# TRI-LIMIT-INTERFACE.net
KiCad netlist of a schematic drawn in EAGLE
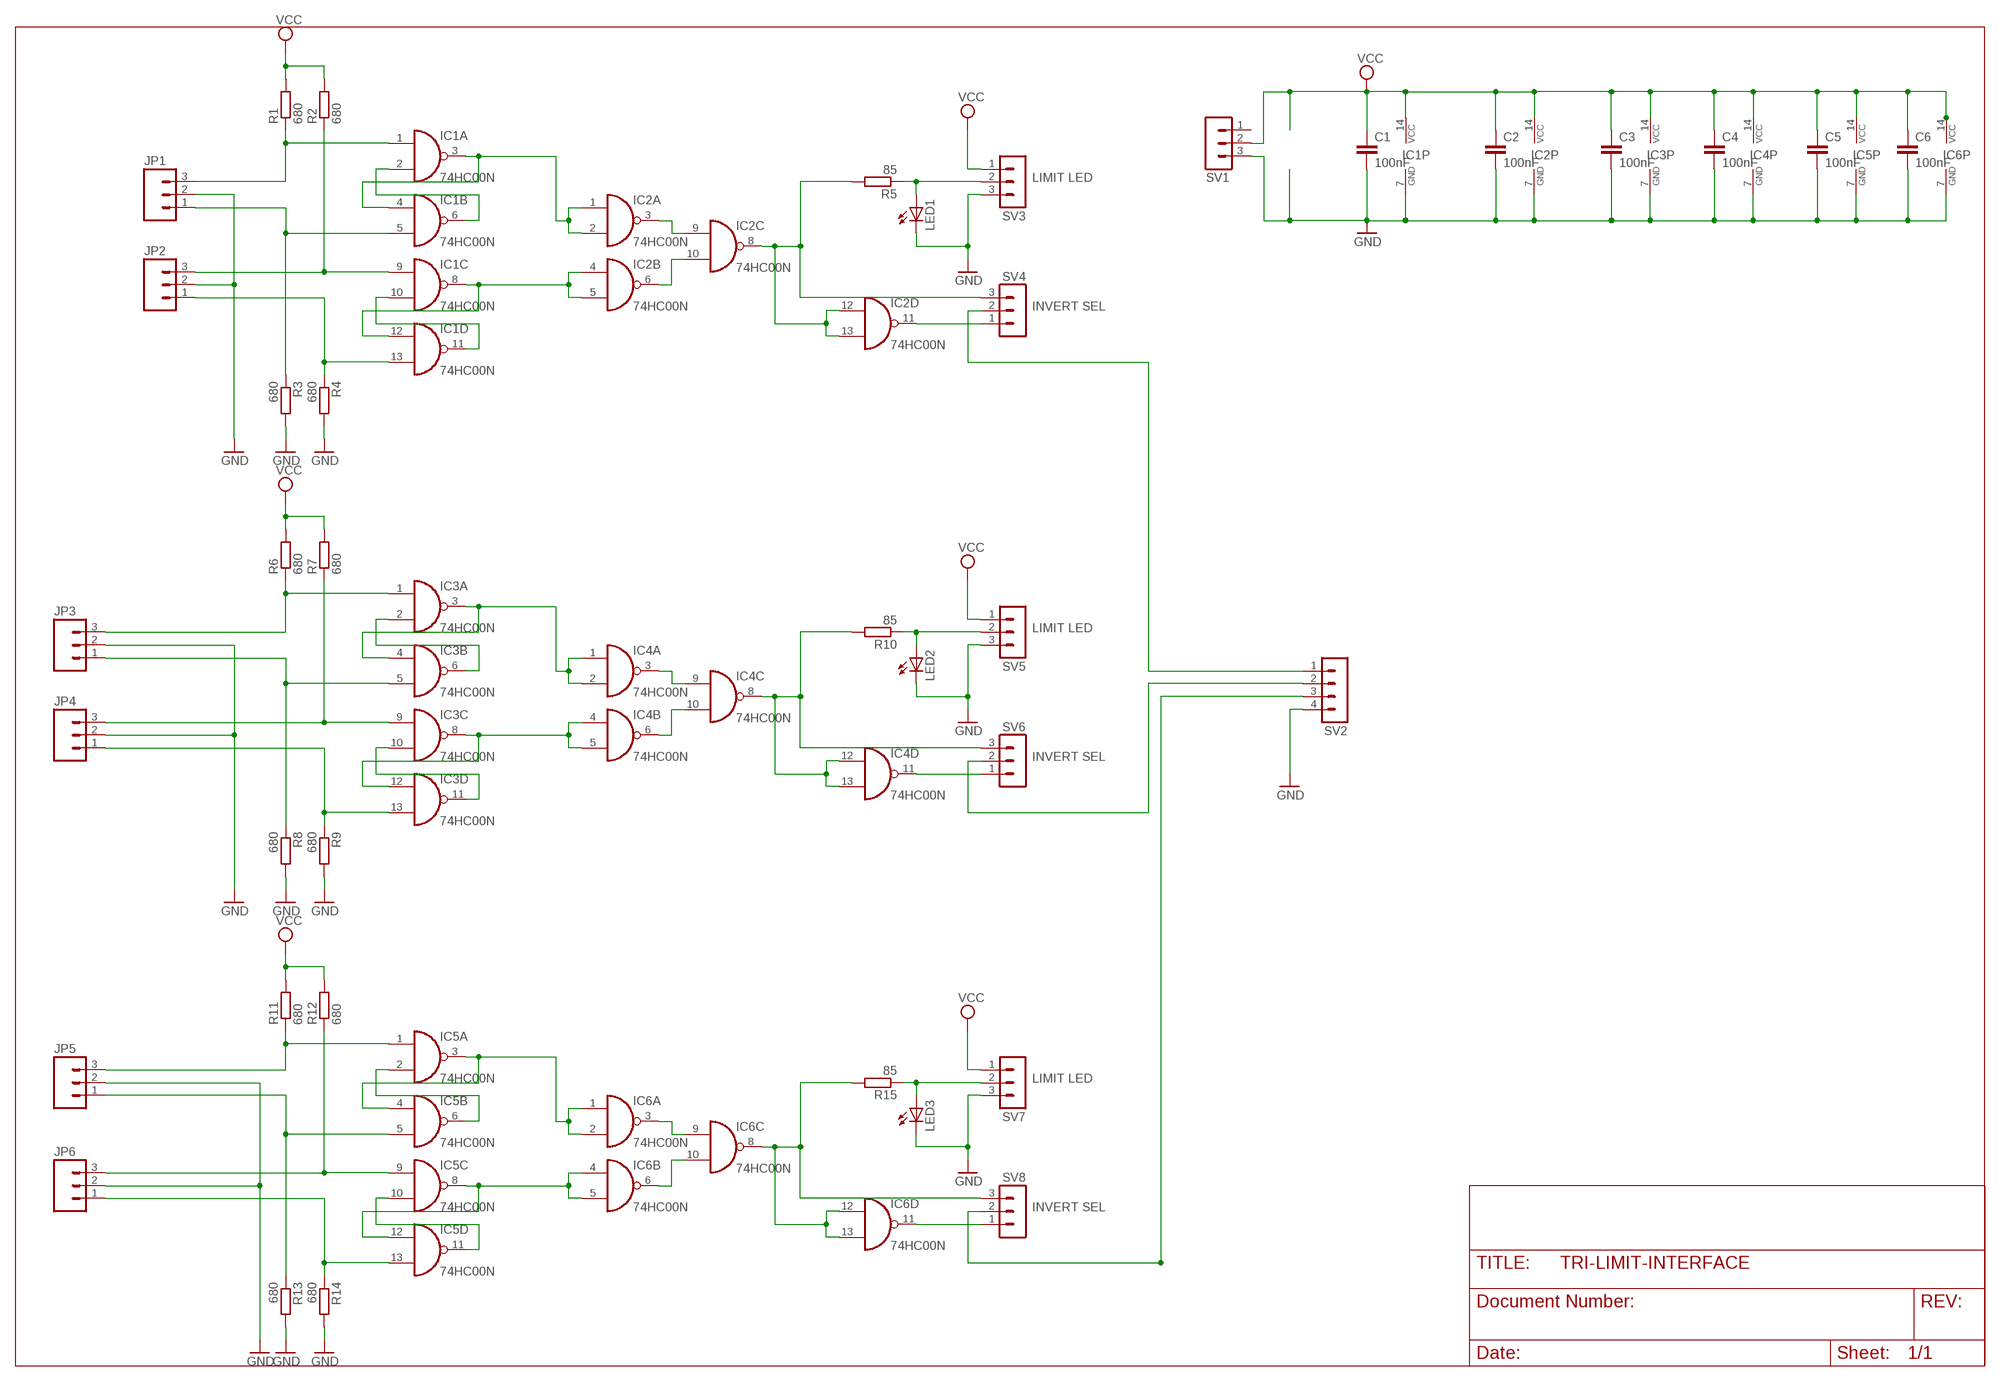
[diagram p0: schematic, sheet 1]

(export (version "E")
  (design (tool "Eeschema 10.0.6"))
  (components
    (comp (ref "C1")
      (value "100nF")
      (footprint "eagle-import:CAP-PTH-SMALL")
      (libsource (lib "eagle-import") (part "CAPPTH"))
    )
    (comp (ref "C2")
      (value "100nF")
      (footprint "eagle-import:CAP-PTH-SMALL")
      (libsource (lib "eagle-import") (part "CAPPTH"))
    )
    (comp (ref "C3")
      (value "100nF")
      (footprint "eagle-import:CAP-PTH-SMALL")
      (libsource (lib "eagle-import") (part "CAPPTH"))
    )
    (comp (ref "C4")
      (value "100nF")
      (footprint "eagle-import:CAP-PTH-SMALL")
      (libsource (lib "eagle-import") (part "CAPPTH"))
    )
    (comp (ref "C5")
      (value "100nF")
      (footprint "eagle-import:CAP-PTH-SMALL")
      (libsource (lib "eagle-import") (part "CAPPTH"))
    )
    (comp (ref "C6")
      (value "100nF")
      (footprint "eagle-import:CAP-PTH-SMALL")
      (libsource (lib "eagle-import") (part "CAPPTH"))
    )
    (comp (ref "IC1")
      (value "74HC00N")
      (footprint "eagle-import:DIL14")
      (libsource (lib "eagle-import") (part "7400NHC"))
    )
    (comp (ref "IC2")
      (value "74HC00N")
      (footprint "eagle-import:DIL14")
      (libsource (lib "eagle-import") (part "7400NHC"))
    )
    (comp (ref "IC3")
      (value "74HC00N")
      (footprint "eagle-import:DIL14")
      (libsource (lib "eagle-import") (part "7400NHC"))
    )
    (comp (ref "IC4")
      (value "74HC00N")
      (footprint "eagle-import:DIL14")
      (libsource (lib "eagle-import") (part "7400NHC"))
    )
    (comp (ref "IC5")
      (value "74HC00N")
      (footprint "eagle-import:DIL14")
      (libsource (lib "eagle-import") (part "7400NHC"))
    )
    (comp (ref "IC6")
      (value "74HC00N")
      (footprint "eagle-import:DIL14")
      (libsource (lib "eagle-import") (part "7400NHC"))
    )
    (comp (ref "JP1")
      (value "M03-SCREW-5MM")
      (footprint "eagle-import:SCREWTERMINAL-5MM-3")
      (libsource (lib "eagle-import") (part "M03-SCREW-5MM"))
    )
    (comp (ref "JP2")
      (value "M03-SCREW-5MM")
      (footprint "eagle-import:SCREWTERMINAL-5MM-3")
      (libsource (lib "eagle-import") (part "M03-SCREW-5MM"))
    )
    (comp (ref "JP3")
      (value "M03-SCREW-5MM")
      (footprint "eagle-import:SCREWTERMINAL-5MM-3")
      (libsource (lib "eagle-import") (part "M03-SCREW-5MM"))
    )
    (comp (ref "JP4")
      (value "M03-SCREW-5MM")
      (footprint "eagle-import:SCREWTERMINAL-5MM-3")
      (libsource (lib "eagle-import") (part "M03-SCREW-5MM"))
    )
    (comp (ref "JP5")
      (value "M03-SCREW-5MM")
      (footprint "eagle-import:SCREWTERMINAL-5MM-3")
      (libsource (lib "eagle-import") (part "M03-SCREW-5MM"))
    )
    (comp (ref "JP6")
      (value "M03-SCREW-5MM")
      (footprint "eagle-import:SCREWTERMINAL-5MM-3")
      (libsource (lib "eagle-import") (part "M03-SCREW-5MM"))
    )
    (comp (ref "LED1")
      (value "LED3MM")
      (footprint "eagle-import:LED3MM")
      (libsource (lib "eagle-import") (part "LED3MM"))
    )
    (comp (ref "LED2")
      (value "LED3MM")
      (footprint "eagle-import:LED3MM")
      (libsource (lib "eagle-import") (part "LED3MM"))
    )
    (comp (ref "LED3")
      (value "LED3MM")
      (footprint "eagle-import:LED3MM")
      (libsource (lib "eagle-import") (part "LED3MM"))
    )
    (comp (ref "R1")
      (value "680")
      (footprint "eagle-import:0207_7")
      (libsource (lib "eagle-import") (part "R-EU_0207/7"))
    )
    (comp (ref "R2")
      (value "680")
      (footprint "eagle-import:0207_7")
      (libsource (lib "eagle-import") (part "R-EU_0207/7"))
    )
    (comp (ref "R3")
      (value "680")
      (footprint "eagle-import:0207_7")
      (libsource (lib "eagle-import") (part "R-EU_0207/7"))
    )
    (comp (ref "R4")
      (value "680")
      (footprint "eagle-import:0207_7")
      (libsource (lib "eagle-import") (part "R-EU_0207/7"))
    )
    (comp (ref "R5")
      (value "85")
      (footprint "eagle-import:0207_10")
      (libsource (lib "eagle-import") (part "R-EU_0207/10"))
    )
    (comp (ref "R6")
      (value "680")
      (footprint "eagle-import:0207_7")
      (libsource (lib "eagle-import") (part "R-EU_0207/7"))
    )
    (comp (ref "R7")
      (value "680")
      (footprint "eagle-import:0207_7")
      (libsource (lib "eagle-import") (part "R-EU_0207/7"))
    )
    (comp (ref "R8")
      (value "680")
      (footprint "eagle-import:0207_7")
      (libsource (lib "eagle-import") (part "R-EU_0207/7"))
    )
    (comp (ref "R9")
      (value "680")
      (footprint "eagle-import:0207_7")
      (libsource (lib "eagle-import") (part "R-EU_0207/7"))
    )
    (comp (ref "R10")
      (value "85")
      (footprint "eagle-import:0207_10")
      (libsource (lib "eagle-import") (part "R-EU_0207/10"))
    )
    (comp (ref "R11")
      (value "680")
      (footprint "eagle-import:0207_7")
      (libsource (lib "eagle-import") (part "R-EU_0207/7"))
    )
    (comp (ref "R12")
      (value "680")
      (footprint "eagle-import:0207_7")
      (libsource (lib "eagle-import") (part "R-EU_0207/7"))
    )
    (comp (ref "R13")
      (value "680")
      (footprint "eagle-import:0207_7")
      (libsource (lib "eagle-import") (part "R-EU_0207/7"))
    )
    (comp (ref "R14")
      (value "680")
      (footprint "eagle-import:0207_7")
      (libsource (lib "eagle-import") (part "R-EU_0207/7"))
    )
    (comp (ref "R15")
      (value "85")
      (footprint "eagle-import:0207_10")
      (libsource (lib "eagle-import") (part "R-EU_0207/10"))
    )
    (comp (ref "SV1")
      (value "MA03-1")
      (footprint "eagle-import:MA03-1")
      (libsource (lib "eagle-import") (part "MA03-1"))
    )
    (comp (ref "SV2")
      (value "MA04-1")
      (footprint "eagle-import:MA04-1")
      (libsource (lib "eagle-import") (part "MA04-1"))
    )
    (comp (ref "SV3")
      (value "MA03-1")
      (footprint "eagle-import:MA03-1")
      (libsource (lib "eagle-import") (part "MA03-1"))
    )
    (comp (ref "SV4")
      (value "MA03-1")
      (footprint "eagle-import:MA03-1")
      (libsource (lib "eagle-import") (part "MA03-1"))
    )
    (comp (ref "SV5")
      (value "MA03-1")
      (footprint "eagle-import:MA03-1")
      (libsource (lib "eagle-import") (part "MA03-1"))
    )
    (comp (ref "SV6")
      (value "MA03-1")
      (footprint "eagle-import:MA03-1")
      (libsource (lib "eagle-import") (part "MA03-1"))
    )
    (comp (ref "SV7")
      (value "MA03-1")
      (footprint "eagle-import:MA03-1")
      (libsource (lib "eagle-import") (part "MA03-1"))
    )
    (comp (ref "SV8")
      (value "MA03-1")
      (footprint "eagle-import:MA03-1")
      (libsource (lib "eagle-import") (part "MA03-1"))
    )
  )
  (nets
    (net (code "1") (name "GND") (class "Default")
      (node (ref "C1") (pin "2") (pinfunction "2_2") (pintype "passive"))
      (node (ref "C2") (pin "2") (pinfunction "2_2") (pintype "passive"))
      (node (ref "C3") (pin "2") (pinfunction "2_2") (pintype "passive"))
      (node (ref "C4") (pin "2") (pinfunction "2_2") (pintype "passive"))
      (node (ref "C5") (pin "2") (pinfunction "2_2") (pintype "passive"))
      (node (ref "C6") (pin "2") (pinfunction "2_2") (pintype "passive"))
      (node (ref "IC1") (pin "7") (pinfunction "GND_7") (pintype "power_in"))
      (node (ref "IC2") (pin "7") (pinfunction "GND_7") (pintype "power_in"))
      (node (ref "IC3") (pin "7") (pinfunction "GND_7") (pintype "power_in"))
      (node (ref "IC4") (pin "7") (pinfunction "GND_7") (pintype "power_in"))
      (node (ref "IC5") (pin "7") (pinfunction "GND_7") (pintype "power_in"))
      (node (ref "IC6") (pin "7") (pinfunction "GND_7") (pintype "power_in"))
      (node (ref "JP1") (pin "2") (pinfunction "2_2") (pintype "passive"))
      (node (ref "JP2") (pin "2") (pinfunction "2_2") (pintype "passive"))
      (node (ref "JP3") (pin "2") (pinfunction "2_2") (pintype "passive"))
      (node (ref "JP4") (pin "2") (pinfunction "2_2") (pintype "passive"))
      (node (ref "JP5") (pin "2") (pinfunction "2_2") (pintype "passive"))
      (node (ref "JP6") (pin "2") (pinfunction "2_2") (pintype "passive"))
      (node (ref "LED1") (pin "K") (pinfunction "C_K") (pintype "passive"))
      (node (ref "LED2") (pin "K") (pinfunction "C_K") (pintype "passive"))
      (node (ref "LED3") (pin "K") (pinfunction "C_K") (pintype "passive"))
      (node (ref "R13") (pin "2") (pinfunction "2_2") (pintype "passive"))
      (node (ref "R14") (pin "2") (pinfunction "2_2") (pintype "passive"))
      (node (ref "R3") (pin "2") (pinfunction "2_2") (pintype "passive"))
      (node (ref "R4") (pin "2") (pinfunction "2_2") (pintype "passive"))
      (node (ref "R8") (pin "2") (pinfunction "2_2") (pintype "passive"))
      (node (ref "R9") (pin "2") (pinfunction "2_2") (pintype "passive"))
      (node (ref "SV1") (pin "3") (pinfunction "3_3") (pintype "passive"))
      (node (ref "SV2") (pin "4") (pinfunction "4_4") (pintype "passive"))
      (node (ref "SV3") (pin "3") (pinfunction "3_3") (pintype "passive"))
      (node (ref "SV5") (pin "3") (pinfunction "3_3") (pintype "passive"))
      (node (ref "SV7") (pin "3") (pinfunction "3_3") (pintype "passive"))
    )
    (net (code "2") (name "Net-(IC1A-I0)") (class "Default")
      (node (ref "IC1") (pin "1") (pinfunction "I0_1") (pintype "input"))
      (node (ref "JP1") (pin "3") (pinfunction "3_3") (pintype "passive"))
      (node (ref "R1") (pin "1") (pinfunction "1_1") (pintype "passive"))
    )
    (net (code "3") (name "Net-(IC1A-I1)") (class "Default")
      (node (ref "IC1") (pin "2") (pinfunction "I1_2") (pintype "input"))
      (node (ref "IC1") (pin "6") (pinfunction "O_6") (pintype "output"))
    )
    (net (code "4") (name "Net-(IC1A-O)") (class "Default")
      (node (ref "IC1") (pin "3") (pinfunction "O_3") (pintype "output"))
      (node (ref "IC1") (pin "4") (pinfunction "I0_4") (pintype "input"))
      (node (ref "IC2") (pin "1") (pinfunction "I0_1") (pintype "input"))
      (node (ref "IC2") (pin "2") (pinfunction "I1_2") (pintype "input"))
    )
    (net (code "5") (name "Net-(IC1B-I1)") (class "Default")
      (node (ref "IC1") (pin "5") (pinfunction "I1_5") (pintype "input"))
      (node (ref "JP1") (pin "1") (pinfunction "1_1") (pintype "passive"))
      (node (ref "R3") (pin "1") (pinfunction "1_1") (pintype "passive"))
    )
    (net (code "6") (name "Net-(IC1C-I0)") (class "Default")
      (node (ref "IC1") (pin "9") (pinfunction "I0_9") (pintype "input"))
      (node (ref "JP2") (pin "3") (pinfunction "3_3") (pintype "passive"))
      (node (ref "R2") (pin "1") (pinfunction "1_1") (pintype "passive"))
    )
    (net (code "7") (name "Net-(IC1C-I1)") (class "Default")
      (node (ref "IC1") (pin "10") (pinfunction "I1_10") (pintype "input"))
      (node (ref "IC1") (pin "11") (pinfunction "O_11") (pintype "output"))
    )
    (net (code "8") (name "Net-(IC1C-O)") (class "Default")
      (node (ref "IC1") (pin "12") (pinfunction "I0_12") (pintype "input"))
      (node (ref "IC1") (pin "8") (pinfunction "O_8") (pintype "output"))
      (node (ref "IC2") (pin "4") (pinfunction "I0_4") (pintype "input"))
      (node (ref "IC2") (pin "5") (pinfunction "I1_5") (pintype "input"))
    )
    (net (code "9") (name "Net-(IC1D-I1)") (class "Default")
      (node (ref "IC1") (pin "13") (pinfunction "I1_13") (pintype "input"))
      (node (ref "JP2") (pin "1") (pinfunction "1_1") (pintype "passive"))
      (node (ref "R4") (pin "1") (pinfunction "1_1") (pintype "passive"))
    )
    (net (code "10") (name "Net-(IC2A-O)") (class "Default")
      (node (ref "IC2") (pin "3") (pinfunction "O_3") (pintype "output"))
      (node (ref "IC2") (pin "9") (pinfunction "I0_9") (pintype "input"))
    )
    (net (code "11") (name "Net-(IC2B-O)") (class "Default")
      (node (ref "IC2") (pin "10") (pinfunction "I1_10") (pintype "input"))
      (node (ref "IC2") (pin "6") (pinfunction "O_6") (pintype "output"))
    )
    (net (code "12") (name "Net-(IC2C-O)") (class "Default")
      (node (ref "IC2") (pin "12") (pinfunction "I0_12") (pintype "input"))
      (node (ref "IC2") (pin "13") (pinfunction "I1_13") (pintype "input"))
      (node (ref "IC2") (pin "8") (pinfunction "O_8") (pintype "output"))
      (node (ref "R5") (pin "2") (pinfunction "2_2") (pintype "passive"))
      (node (ref "SV4") (pin "3") (pinfunction "3_3") (pintype "passive"))
    )
    (net (code "13") (name "Net-(IC2D-O)") (class "Default")
      (node (ref "IC2") (pin "11") (pinfunction "O_11") (pintype "output"))
      (node (ref "SV4") (pin "1") (pinfunction "1_1") (pintype "passive"))
    )
    (net (code "14") (name "Net-(IC3A-I0)") (class "Default")
      (node (ref "IC3") (pin "1") (pinfunction "I0_1") (pintype "input"))
      (node (ref "JP3") (pin "3") (pinfunction "3_3") (pintype "passive"))
      (node (ref "R6") (pin "1") (pinfunction "1_1") (pintype "passive"))
    )
    (net (code "15") (name "Net-(IC3A-I1)") (class "Default")
      (node (ref "IC3") (pin "2") (pinfunction "I1_2") (pintype "input"))
      (node (ref "IC3") (pin "6") (pinfunction "O_6") (pintype "output"))
    )
    (net (code "16") (name "Net-(IC3A-O)") (class "Default")
      (node (ref "IC3") (pin "3") (pinfunction "O_3") (pintype "output"))
      (node (ref "IC3") (pin "4") (pinfunction "I0_4") (pintype "input"))
      (node (ref "IC4") (pin "1") (pinfunction "I0_1") (pintype "input"))
      (node (ref "IC4") (pin "2") (pinfunction "I1_2") (pintype "input"))
    )
    (net (code "17") (name "Net-(IC3B-I1)") (class "Default")
      (node (ref "IC3") (pin "5") (pinfunction "I1_5") (pintype "input"))
      (node (ref "JP3") (pin "1") (pinfunction "1_1") (pintype "passive"))
      (node (ref "R8") (pin "1") (pinfunction "1_1") (pintype "passive"))
    )
    (net (code "18") (name "Net-(IC3C-I0)") (class "Default")
      (node (ref "IC3") (pin "9") (pinfunction "I0_9") (pintype "input"))
      (node (ref "JP4") (pin "3") (pinfunction "3_3") (pintype "passive"))
      (node (ref "R7") (pin "1") (pinfunction "1_1") (pintype "passive"))
    )
    (net (code "19") (name "Net-(IC3C-I1)") (class "Default")
      (node (ref "IC3") (pin "10") (pinfunction "I1_10") (pintype "input"))
      (node (ref "IC3") (pin "11") (pinfunction "O_11") (pintype "output"))
    )
    (net (code "20") (name "Net-(IC3C-O)") (class "Default")
      (node (ref "IC3") (pin "12") (pinfunction "I0_12") (pintype "input"))
      (node (ref "IC3") (pin "8") (pinfunction "O_8") (pintype "output"))
      (node (ref "IC4") (pin "4") (pinfunction "I0_4") (pintype "input"))
      (node (ref "IC4") (pin "5") (pinfunction "I1_5") (pintype "input"))
    )
    (net (code "21") (name "Net-(IC3D-I1)") (class "Default")
      (node (ref "IC3") (pin "13") (pinfunction "I1_13") (pintype "input"))
      (node (ref "JP4") (pin "1") (pinfunction "1_1") (pintype "passive"))
      (node (ref "R9") (pin "1") (pinfunction "1_1") (pintype "passive"))
    )
    (net (code "22") (name "Net-(IC4A-O)") (class "Default")
      (node (ref "IC4") (pin "3") (pinfunction "O_3") (pintype "output"))
      (node (ref "IC4") (pin "9") (pinfunction "I0_9") (pintype "input"))
    )
    (net (code "23") (name "Net-(IC4B-O)") (class "Default")
      (node (ref "IC4") (pin "10") (pinfunction "I1_10") (pintype "input"))
      (node (ref "IC4") (pin "6") (pinfunction "O_6") (pintype "output"))
    )
    (net (code "24") (name "Net-(IC4C-O)") (class "Default")
      (node (ref "IC4") (pin "12") (pinfunction "I0_12") (pintype "input"))
      (node (ref "IC4") (pin "13") (pinfunction "I1_13") (pintype "input"))
      (node (ref "IC4") (pin "8") (pinfunction "O_8") (pintype "output"))
      (node (ref "R10") (pin "2") (pinfunction "2_2") (pintype "passive"))
      (node (ref "SV6") (pin "3") (pinfunction "3_3") (pintype "passive"))
    )
    (net (code "25") (name "Net-(IC4D-O)") (class "Default")
      (node (ref "IC4") (pin "11") (pinfunction "O_11") (pintype "output"))
      (node (ref "SV6") (pin "1") (pinfunction "1_1") (pintype "passive"))
    )
    (net (code "26") (name "Net-(IC5A-I0)") (class "Default")
      (node (ref "IC5") (pin "1") (pinfunction "I0_1") (pintype "input"))
      (node (ref "JP5") (pin "3") (pinfunction "3_3") (pintype "passive"))
      (node (ref "R11") (pin "1") (pinfunction "1_1") (pintype "passive"))
    )
    (net (code "27") (name "Net-(IC5A-I1)") (class "Default")
      (node (ref "IC5") (pin "2") (pinfunction "I1_2") (pintype "input"))
      (node (ref "IC5") (pin "6") (pinfunction "O_6") (pintype "output"))
    )
    (net (code "28") (name "Net-(IC5A-O)") (class "Default")
      (node (ref "IC5") (pin "3") (pinfunction "O_3") (pintype "output"))
      (node (ref "IC5") (pin "4") (pinfunction "I0_4") (pintype "input"))
      (node (ref "IC6") (pin "1") (pinfunction "I0_1") (pintype "input"))
      (node (ref "IC6") (pin "2") (pinfunction "I1_2") (pintype "input"))
    )
    (net (code "29") (name "Net-(IC5B-I1)") (class "Default")
      (node (ref "IC5") (pin "5") (pinfunction "I1_5") (pintype "input"))
      (node (ref "JP5") (pin "1") (pinfunction "1_1") (pintype "passive"))
      (node (ref "R13") (pin "1") (pinfunction "1_1") (pintype "passive"))
    )
    (net (code "30") (name "Net-(IC5C-I0)") (class "Default")
      (node (ref "IC5") (pin "9") (pinfunction "I0_9") (pintype "input"))
      (node (ref "JP6") (pin "3") (pinfunction "3_3") (pintype "passive"))
      (node (ref "R12") (pin "1") (pinfunction "1_1") (pintype "passive"))
    )
    (net (code "31") (name "Net-(IC5C-I1)") (class "Default")
      (node (ref "IC5") (pin "10") (pinfunction "I1_10") (pintype "input"))
      (node (ref "IC5") (pin "11") (pinfunction "O_11") (pintype "output"))
    )
    (net (code "32") (name "Net-(IC5C-O)") (class "Default")
      (node (ref "IC5") (pin "12") (pinfunction "I0_12") (pintype "input"))
      (node (ref "IC5") (pin "8") (pinfunction "O_8") (pintype "output"))
      (node (ref "IC6") (pin "4") (pinfunction "I0_4") (pintype "input"))
      (node (ref "IC6") (pin "5") (pinfunction "I1_5") (pintype "input"))
    )
    (net (code "33") (name "Net-(IC5D-I1)") (class "Default")
      (node (ref "IC5") (pin "13") (pinfunction "I1_13") (pintype "input"))
      (node (ref "JP6") (pin "1") (pinfunction "1_1") (pintype "passive"))
      (node (ref "R14") (pin "1") (pinfunction "1_1") (pintype "passive"))
    )
    (net (code "34") (name "Net-(IC6A-O)") (class "Default")
      (node (ref "IC6") (pin "3") (pinfunction "O_3") (pintype "output"))
      (node (ref "IC6") (pin "9") (pinfunction "I0_9") (pintype "input"))
    )
    (net (code "35") (name "Net-(IC6B-O)") (class "Default")
      (node (ref "IC6") (pin "10") (pinfunction "I1_10") (pintype "input"))
      (node (ref "IC6") (pin "6") (pinfunction "O_6") (pintype "output"))
    )
    (net (code "36") (name "Net-(IC6C-O)") (class "Default")
      (node (ref "IC6") (pin "12") (pinfunction "I0_12") (pintype "input"))
      (node (ref "IC6") (pin "13") (pinfunction "I1_13") (pintype "input"))
      (node (ref "IC6") (pin "8") (pinfunction "O_8") (pintype "output"))
      (node (ref "R15") (pin "2") (pinfunction "2_2") (pintype "passive"))
      (node (ref "SV8") (pin "3") (pinfunction "3_3") (pintype "passive"))
    )
    (net (code "37") (name "Net-(IC6D-O)") (class "Default")
      (node (ref "IC6") (pin "11") (pinfunction "O_11") (pintype "output"))
      (node (ref "SV8") (pin "1") (pinfunction "1_1") (pintype "passive"))
    )
    (net (code "38") (name "Net-(LED1-PadA)") (class "Default")
      (node (ref "LED1") (pin "A") (pinfunction "A_A") (pintype "passive"))
      (node (ref "R5") (pin "1") (pinfunction "1_1") (pintype "passive"))
      (node (ref "SV3") (pin "2") (pinfunction "2_2") (pintype "passive"))
    )
    (net (code "39") (name "Net-(LED2-PadA)") (class "Default")
      (node (ref "LED2") (pin "A") (pinfunction "A_A") (pintype "passive"))
      (node (ref "R10") (pin "1") (pinfunction "1_1") (pintype "passive"))
      (node (ref "SV5") (pin "2") (pinfunction "2_2") (pintype "passive"))
    )
    (net (code "40") (name "Net-(LED3-PadA)") (class "Default")
      (node (ref "LED3") (pin "A") (pinfunction "A_A") (pintype "passive"))
      (node (ref "R15") (pin "1") (pinfunction "1_1") (pintype "passive"))
      (node (ref "SV7") (pin "2") (pinfunction "2_2") (pintype "passive"))
    )
    (net (code "41") (name "Net-(SV2-Pad1)") (class "Default")
      (node (ref "SV2") (pin "1") (pinfunction "1_1") (pintype "passive"))
      (node (ref "SV4") (pin "2") (pinfunction "2_2") (pintype "passive"))
    )
    (net (code "42") (name "Net-(SV2-Pad2)") (class "Default")
      (node (ref "SV2") (pin "2") (pinfunction "2_2") (pintype "passive"))
      (node (ref "SV6") (pin "2") (pinfunction "2_2") (pintype "passive"))
    )
    (net (code "43") (name "Net-(SV2-Pad3)") (class "Default")
      (node (ref "SV2") (pin "3") (pinfunction "3_3") (pintype "passive"))
      (node (ref "SV8") (pin "2") (pinfunction "2_2") (pintype "passive"))
    )
    (net (code "44") (name "VCC") (class "Default")
      (node (ref "C1") (pin "1") (pinfunction "1_1") (pintype "passive"))
      (node (ref "C2") (pin "1") (pinfunction "1_1") (pintype "passive"))
      (node (ref "C3") (pin "1") (pinfunction "1_1") (pintype "passive"))
      (node (ref "C4") (pin "1") (pinfunction "1_1") (pintype "passive"))
      (node (ref "C5") (pin "1") (pinfunction "1_1") (pintype "passive"))
      (node (ref "C6") (pin "1") (pinfunction "1_1") (pintype "passive"))
      (node (ref "IC1") (pin "14") (pinfunction "VCC_14") (pintype "power_in"))
      (node (ref "IC2") (pin "14") (pinfunction "VCC_14") (pintype "power_in"))
      (node (ref "IC3") (pin "14") (pinfunction "VCC_14") (pintype "power_in"))
      (node (ref "IC4") (pin "14") (pinfunction "VCC_14") (pintype "power_in"))
      (node (ref "IC5") (pin "14") (pinfunction "VCC_14") (pintype "power_in"))
      (node (ref "IC6") (pin "14") (pinfunction "VCC_14") (pintype "power_in"))
      (node (ref "R1") (pin "2") (pinfunction "2_2") (pintype "passive"))
      (node (ref "R11") (pin "2") (pinfunction "2_2") (pintype "passive"))
      (node (ref "R12") (pin "2") (pinfunction "2_2") (pintype "passive"))
      (node (ref "R2") (pin "2") (pinfunction "2_2") (pintype "passive"))
      (node (ref "R6") (pin "2") (pinfunction "2_2") (pintype "passive"))
      (node (ref "R7") (pin "2") (pinfunction "2_2") (pintype "passive"))
      (node (ref "SV1") (pin "2") (pinfunction "2_2") (pintype "passive"))
      (node (ref "SV3") (pin "1") (pinfunction "1_1") (pintype "passive"))
      (node (ref "SV5") (pin "1") (pinfunction "1_1") (pintype "passive"))
      (node (ref "SV7") (pin "1") (pinfunction "1_1") (pintype "passive"))
    )
    (net (code "45") (name "unconnected-(SV1-Pad1)") (class "Default")
      (node (ref "SV1") (pin "1") (pinfunction "1_1") (pintype "passive"))
    )
  )
)
